# MCU.net
KiCad netlist of a schematic drawn in Altium Designer
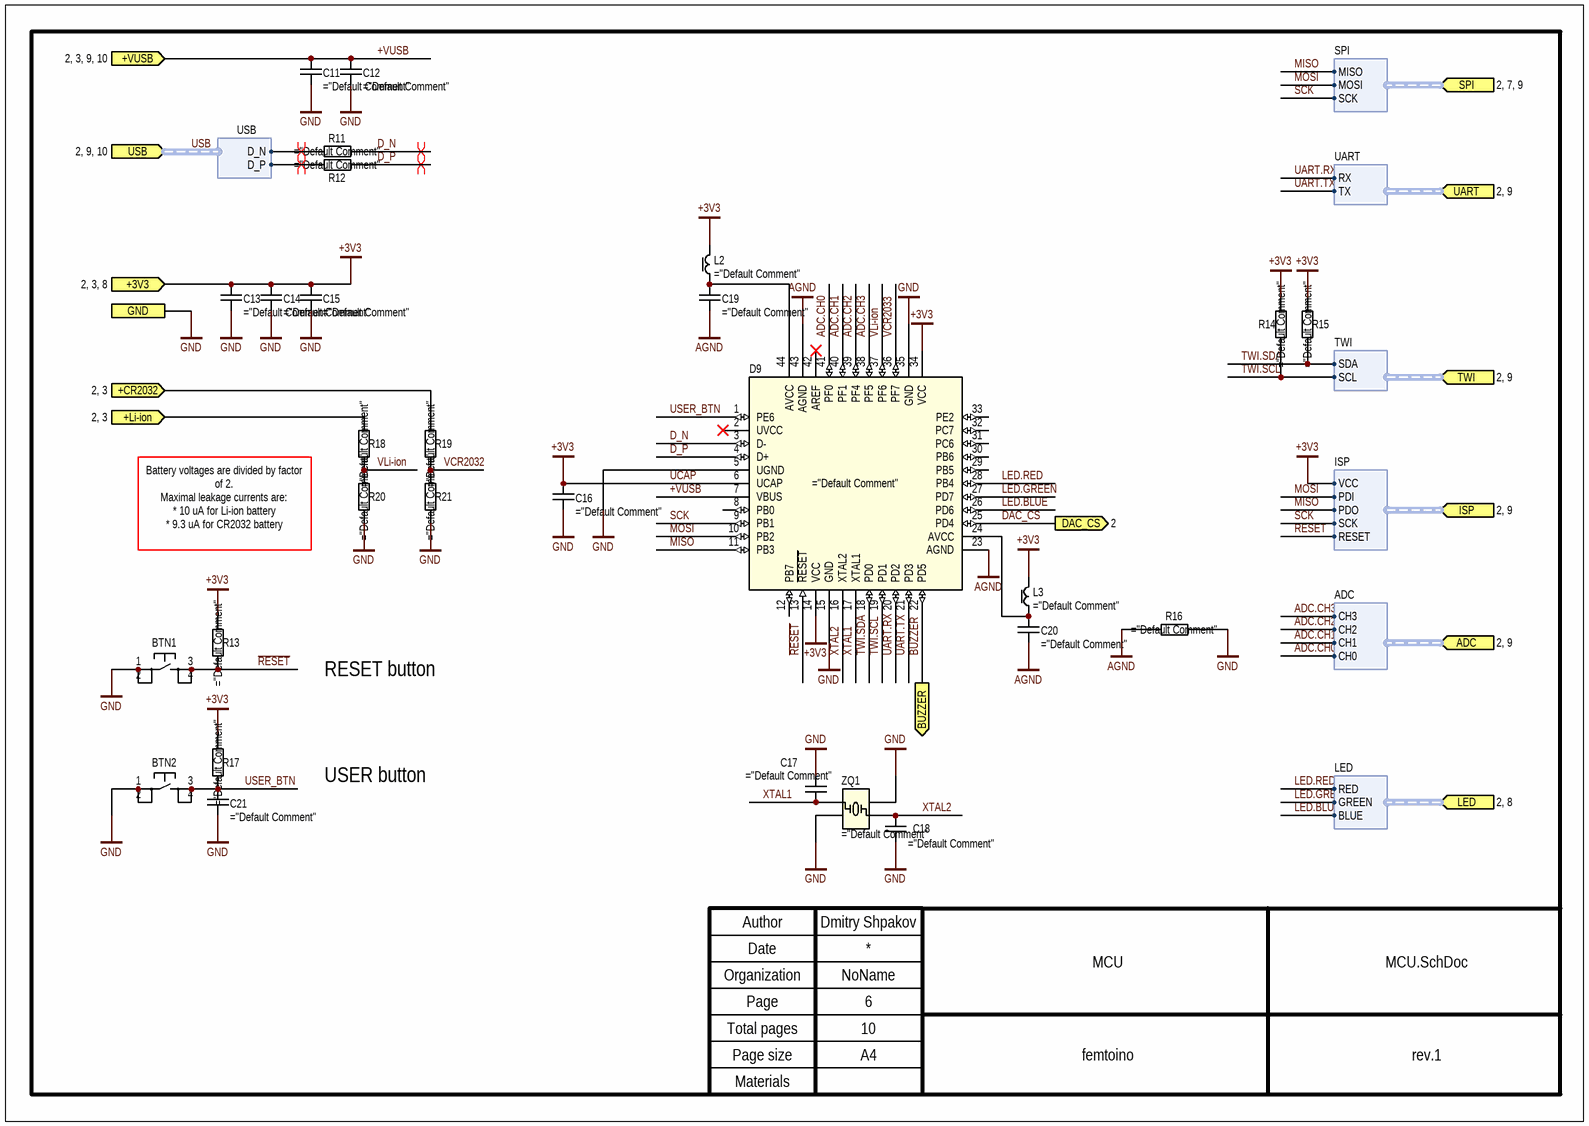
[diagram p0: MCU.SchDoc]

(export (version "E")
  (design (tool "Eeschema 10.0.6"))
  (components
    (comp (ref "BTN1")
      (value "~")
      (description "SWITCH TACTILE SPST-NO 0.05A 16V")
      (fields (field (name "TOLERANCE") "* %") (field (name "MANUFACTURER") "C&K"))
      (libsource (lib "femtoino") (part "PTS810 SJK 250 SMTR LFS"))
    )
    (comp (ref "BTN2")
      (value "~")
      (description "SWITCH TACTILE SPST-NO 0.05A 16V")
      (fields (field (name "TOLERANCE") "* %") (field (name "MANUFACTURER") "C&K"))
      (libsource (lib "femtoino") (part "PTS810 SJK 250 SMTR LFS"))
    )
    (comp (ref "C11")
      (value "~")
      (description "CAP CER 10UF 10V X5R 0805")
      (fields (field (name "TOLERANCE") "10 %") (field (name "MANUFACTURER") "YAGEO"))
      (libsource (lib "femtoino") (part "CC0805KPX5R6BB106"))
    )
    (comp (ref "C12")
      (value "~")
      (description "CAP CER 1UF 10V X5R 0805")
      (fields (field (name "TOLERANCE") "10 %") (field (name "MANUFACTURER") "YAGEO"))
      (libsource (lib "femtoino") (part "CC0805KKX5R6BB105"))
    )
    (comp (ref "C13")
      (value "~")
      (description "CAP CER 10UF 10V X5R 0805")
      (fields (field (name "TOLERANCE") "10 %") (field (name "MANUFACTURER") "YAGEO"))
      (libsource (lib "femtoino") (part "CC0805KPX5R6BB106"))
    )
    (comp (ref "C14")
      (value "~")
      (description "CAP CER 10UF 10V X5R 0805")
      (fields (field (name "TOLERANCE") "10 %") (field (name "MANUFACTURER") "YAGEO"))
      (libsource (lib "femtoino") (part "CC0805KPX5R6BB106"))
    )
    (comp (ref "C15")
      (value "~")
      (description "CAP CER 1UF 10V X5R 0805")
      (fields (field (name "TOLERANCE") "10 %") (field (name "MANUFACTURER") "YAGEO"))
      (libsource (lib "femtoino") (part "CC0805KKX5R6BB105"))
    )
    (comp (ref "C16")
      (value "~")
      (description "CAP CER 1UF 10V X5R 0805")
      (fields (field (name "TOLERANCE") "10 %") (field (name "MANUFACTURER") "YAGEO"))
      (libsource (lib "femtoino") (part "CC0805KKX5R6BB105"))
    )
    (comp (ref "C17")
      (value "~")
      (description "CAP CER 12PF 50V C0G/NPO 0603")
      (fields (field (name "TOLERANCE") "5 %") (field (name "MANUFACTURER") "YAGEO"))
      (libsource (lib "femtoino") (part "CC0603JRNPO9BN120"))
    )
    (comp (ref "C18")
      (value "~")
      (description "CAP CER 12PF 50V C0G/NPO 0603")
      (fields (field (name "TOLERANCE") "5 %") (field (name "MANUFACTURER") "YAGEO"))
      (libsource (lib "femtoino") (part "CC0603JRNPO9BN120"))
    )
    (comp (ref "C19")
      (value "~")
      (description "CAP CER 0.1UF 50V X7R 0805")
      (fields (field (name "TOLERANCE") "10 %") (field (name "MANUFACTURER") "YAGEO"))
      (libsource (lib "femtoino") (part "CC0805KRX7R9BB104"))
    )
    (comp (ref "C20")
      (value "~")
      (description "CAP CER 0.1UF 50V X7R 0805")
      (fields (field (name "TOLERANCE") "10 %") (field (name "MANUFACTURER") "YAGEO"))
      (libsource (lib "femtoino") (part "CC0805KRX7R9BB104"))
    )
    (comp (ref "C21")
      (value "~")
      (description "CAP CER 0.1UF 50V X7R 0805")
      (fields (field (name "TOLERANCE") "10 %") (field (name "MANUFACTURER") "YAGEO"))
      (libsource (lib "femtoino") (part "CC0805KRX7R9BB104"))
    )
    (comp (ref "D9")
      (value "~")
      (description "IC MCU 8BIT 32KB FLASH 44VQFN")
      (fields (field (name "TOLERANCE") "* %") (field (name "MANUFACTURER") "Microchip Technology"))
      (libsource (lib "femtoino") (part "ATMEGA32U4-MU"))
    )
    (comp (ref "L2")
      (value "~")
      (description "FIXED IND 10UH 850MA 300MOHM SMD")
      (fields (field (name "TOLERANCE") "* %") (field (name "MANUFACTURER") "Würth Elektronik"))
      (libsource (lib "femtoino") (part "74479887310A"))
    )
    (comp (ref "L3")
      (value "~")
      (description "FIXED IND 10UH 850MA 300MOHM SMD")
      (fields (field (name "TOLERANCE") "* %") (field (name "MANUFACTURER") "Würth Elektronik"))
      (libsource (lib "femtoino") (part "74479887310A"))
    )
    (comp (ref "R11")
      (value "~")
      (description "RES 22 OHM 1% 1/10W 0603")
      (fields (field (name "TOLERANCE") "1 %") (field (name "MANUFACTURER") "YAGEO"))
      (libsource (lib "femtoino") (part "RC0603FR-0722RL"))
    )
    (comp (ref "R12")
      (value "~")
      (description "RES 22 OHM 1% 1/10W 0603")
      (fields (field (name "TOLERANCE") "1 %") (field (name "MANUFACTURER") "YAGEO"))
      (libsource (lib "femtoino") (part "RC0603FR-0722RL"))
    )
    (comp (ref "R13")
      (value "~")
      (description "RES 62K OHM 1% 1/10W 0603")
      (fields (field (name "TOLERANCE") "1 %") (field (name "MANUFACTURER") "YAGEO"))
      (libsource (lib "femtoino") (part "RC0603FR-0762KL"))
    )
    (comp (ref "R14")
      (value "~")
      (description "RES 5.1K OHM 1% 1/10W 0603")
      (fields (field (name "TOLERANCE") "1 %") (field (name "MANUFACTURER") "YAGEO"))
      (libsource (lib "femtoino") (part "RC0603FR-075K1L"))
    )
    (comp (ref "R15")
      (value "~")
      (description "RES 5.1K OHM 1% 1/10W 0603")
      (fields (field (name "TOLERANCE") "1 %") (field (name "MANUFACTURER") "YAGEO"))
      (libsource (lib "femtoino") (part "RC0603FR-075K1L"))
    )
    (comp (ref "R16")
      (value "~")
      (description "RES 0 OHM JUMPER 1/10W 0603")
      (fields (field (name "TOLERANCE") "* %") (field (name "MANUFACTURER") "YAGEO"))
      (libsource (lib "femtoino") (part "RC0603JR-070RL"))
    )
    (comp (ref "R17")
      (value "~")
      (description "RES 62K OHM 1% 1/10W 0603")
      (fields (field (name "TOLERANCE") "1 %") (field (name "MANUFACTURER") "YAGEO"))
      (libsource (lib "femtoino") (part "RC0603FR-0762KL"))
    )
    (comp (ref "R18")
      (value "~")
      (description "RES 200K OHM 1% 1/10W 0603")
      (fields (field (name "TOLERANCE") "1 %") (field (name "MANUFACTURER") "YAGEO"))
      (libsource (lib "femtoino") (part "RC0603FR-07200KL"))
    )
    (comp (ref "R19")
      (value "~")
      (description "RES 200K OHM 1% 1/10W 0603")
      (fields (field (name "TOLERANCE") "1 %") (field (name "MANUFACTURER") "YAGEO"))
      (libsource (lib "femtoino") (part "RC0603FR-07200KL"))
    )
    (comp (ref "R20")
      (value "~")
      (description "RES 200K OHM 1% 1/10W 0603")
      (fields (field (name "TOLERANCE") "1 %") (field (name "MANUFACTURER") "YAGEO"))
      (libsource (lib "femtoino") (part "RC0603FR-07200KL"))
    )
    (comp (ref "R21")
      (value "~")
      (description "RES 200K OHM 1% 1/10W 0603")
      (fields (field (name "TOLERANCE") "1 %") (field (name "MANUFACTURER") "YAGEO"))
      (libsource (lib "femtoino") (part "RC0603FR-07200KL"))
    )
    (comp (ref "ZQ1")
      (value "~")
      (description "CRYSTAL 8.0000MHZ 12PF SMD")
      (fields (field (name "TOLERANCE") "20 ppm") (field (name "MANUFACTURER") "ECS Inc."))
      (libsource (lib "femtoino") (part "ECS-80-12-33-JGN-TR"))
    )
  )
  (nets
    (net (code "8") (name "+3V3") (class "Default")
      (node (ref "C13") (pin "2") (pinfunction "2_2") (pintype "passive"))
      (node (ref "C14") (pin "2") (pinfunction "2_2") (pintype "passive"))
      (node (ref "C15") (pin "2") (pinfunction "2_2") (pintype "passive"))
      (node (ref "C16") (pin "2") (pinfunction "2_2") (pintype "passive"))
      (node (ref "D9") (pin "14") (pinfunction "VCC_14") (pintype "passive"))
      (node (ref "D9") (pin "34") (pinfunction "VCC_34") (pintype "passive"))
      (node (ref "D9") (pin "6") (pinfunction "UCAP_6") (pintype "passive"))
      (node (ref "L2") (pin "2") (pinfunction "2_2") (pintype "passive"))
      (node (ref "L3") (pin "2") (pinfunction "2_2") (pintype "passive"))
      (node (ref "R13") (pin "2") (pinfunction "2_2") (pintype "passive"))
      (node (ref "R14") (pin "2") (pinfunction "2_2") (pintype "passive"))
      (node (ref "R15") (pin "2") (pinfunction "2_2") (pintype "passive"))
      (node (ref "R17") (pin "2") (pinfunction "2_2") (pintype "passive"))
    )
    (net (code "9") (name "/+CR2032") (class "Default")
      (node (ref "R19") (pin "2") (pinfunction "2_2") (pintype "passive"))
    )
    (net (code "10") (name "/+Li-ion") (class "Default")
      (node (ref "R18") (pin "2") (pinfunction "2_2") (pintype "passive"))
    )
    (net (code "11") (name "/+VUSB") (class "Default")
      (node (ref "C11") (pin "2") (pinfunction "2_2") (pintype "passive"))
      (node (ref "C12") (pin "2") (pinfunction "2_2") (pintype "passive"))
      (node (ref "D9") (pin "7") (pinfunction "VBUS_7") (pintype "passive"))
    )
    (net (code "12") (name "/ADC.CH0") (class "Default")
      (node (ref "D9") (pin "41") (pinfunction "PF0_41") (pintype "bidirectional"))
    )
    (net (code "13") (name "/ADC.CH1") (class "Default")
      (node (ref "D9") (pin "40") (pinfunction "PF1_40") (pintype "bidirectional"))
    )
    (net (code "14") (name "/ADC.CH2") (class "Default")
      (node (ref "D9") (pin "39") (pinfunction "PF4_39") (pintype "bidirectional"))
    )
    (net (code "15") (name "/ADC.CH3") (class "Default")
      (node (ref "D9") (pin "38") (pinfunction "PF5_38") (pintype "bidirectional"))
    )
    (net (code "16") (name "/BUZZER") (class "Default")
      (node (ref "D9") (pin "22") (pinfunction "PD5_22") (pintype "bidirectional"))
    )
    (net (code "17") (name "/DAC_CS") (class "Default")
      (node (ref "D9") (pin "25") (pinfunction "PD4_25") (pintype "bidirectional"))
    )
    (net (code "18") (name "/D_N") (class "Default")
      (node (ref "D9") (pin "3") (pinfunction "D-_3") (pintype "bidirectional"))
      (node (ref "R11") (pin "2") (pinfunction "2_2") (pintype "passive"))
    )
    (net (code "19") (name "/D_P") (class "Default")
      (node (ref "D9") (pin "4") (pinfunction "D+_4") (pintype "bidirectional"))
      (node (ref "R12") (pin "2") (pinfunction "2_2") (pintype "passive"))
    )
    (net (code "20") (name "/LED.BLUE") (class "Default")
      (node (ref "D9") (pin "26") (pinfunction "PD6_26") (pintype "bidirectional"))
    )
    (net (code "21") (name "/LED.GREEN") (class "Default")
      (node (ref "D9") (pin "27") (pinfunction "PD7_27") (pintype "bidirectional"))
    )
    (net (code "22") (name "/LED.RED") (class "Default")
      (node (ref "D9") (pin "28") (pinfunction "PB4_28") (pintype "bidirectional"))
    )
    (net (code "23") (name "/MISO") (class "Default")
      (node (ref "D9") (pin "11") (pinfunction "PB3_11") (pintype "bidirectional"))
    )
    (net (code "24") (name "/MOSI") (class "Default")
      (node (ref "D9") (pin "10") (pinfunction "PB2_10") (pintype "bidirectional"))
    )
    (net (code "25") (name "/SCK") (class "Default")
      (node (ref "D9") (pin "9") (pinfunction "PB1_9") (pintype "bidirectional"))
    )
    (net (code "26") (name "/TWI.SCL") (class "Default")
      (node (ref "D9") (pin "19") (pinfunction "PD1_19") (pintype "bidirectional"))
      (node (ref "R14") (pin "1") (pinfunction "1_1") (pintype "passive"))
    )
    (net (code "27") (name "/TWI.SDA") (class "Default")
      (node (ref "D9") (pin "18") (pinfunction "PD0_18") (pintype "bidirectional"))
      (node (ref "R15") (pin "1") (pinfunction "1_1") (pintype "passive"))
    )
    (net (code "28") (name "/UART.RX") (class "Default")
      (node (ref "D9") (pin "20") (pinfunction "PD2_20") (pintype "bidirectional"))
    )
    (net (code "29") (name "/UART.TX") (class "Default")
      (node (ref "D9") (pin "21") (pinfunction "PD3_21") (pintype "bidirectional"))
    )
    (net (code "31") (name "/USER_BTN") (class "Default")
      (node (ref "BTN2") (pin "3") (pinfunction "3_3") (pintype "passive"))
      (node (ref "BTN2") (pin "4") (pinfunction "4_4") (pintype "passive"))
      (node (ref "C21") (pin "2") (pinfunction "2_2") (pintype "passive"))
      (node (ref "D9") (pin "1") (pinfunction "PE6_1") (pintype "bidirectional"))
      (node (ref "R17") (pin "1") (pinfunction "1_1") (pintype "passive"))
    )
    (net (code "32") (name "/VCR2032") (class "Default")
      (node (ref "R19") (pin "1") (pinfunction "1_1") (pintype "passive"))
      (node (ref "R21") (pin "2") (pinfunction "2_2") (pintype "passive"))
    )
    (net (code "33") (name "/VCR2033") (class "Default")
      (node (ref "D9") (pin "36") (pinfunction "PF7_36") (pintype "bidirectional"))
    )
    (net (code "34") (name "/VLi-ion") (class "Default")
      (node (ref "D9") (pin "37") (pinfunction "PF6_37") (pintype "bidirectional"))
      (node (ref "R18") (pin "1") (pinfunction "1_1") (pintype "passive"))
      (node (ref "R20") (pin "2") (pinfunction "2_2") (pintype "passive"))
    )
    (net (code "35") (name "/XTAL1") (class "Default")
      (node (ref "C17") (pin "2") (pinfunction "2_2") (pintype "passive"))
      (node (ref "D9") (pin "17") (pinfunction "XTAL1_17") (pintype "passive"))
      (node (ref "ZQ1") (pin "1") (pinfunction "1_1") (pintype "passive"))
    )
    (net (code "36") (name "/XTAL2") (class "Default")
      (node (ref "C18") (pin "2") (pinfunction "2_2") (pintype "passive"))
      (node (ref "D9") (pin "16") (pinfunction "XTAL2_16") (pintype "passive"))
      (node (ref "ZQ1") (pin "3") (pinfunction "3_3") (pintype "passive"))
    )
    (net (code "43") (name "/~{RESET}") (class "Default")
      (node (ref "BTN1") (pin "3") (pinfunction "3_3") (pintype "passive"))
      (node (ref "BTN1") (pin "4") (pinfunction "4_4") (pintype "passive"))
      (node (ref "D9") (pin "13") (pinfunction "~{RESET}_13") (pintype "input"))
      (node (ref "R13") (pin "1") (pinfunction "1_1") (pintype "passive"))
    )
    (net (code "44") (name "AGND") (class "Default")
      (node (ref "C19") (pin "1") (pinfunction "1_1") (pintype "passive"))
      (node (ref "C20") (pin "1") (pinfunction "1_1") (pintype "passive"))
      (node (ref "D9") (pin "23") (pinfunction "AGND_23") (pintype "passive"))
      (node (ref "D9") (pin "43") (pinfunction "AGND_43") (pintype "passive"))
      (node (ref "R16") (pin "1") (pinfunction "1_1") (pintype "passive"))
    )
    (net (code "45") (name "GND") (class "Default")
      (node (ref "BTN1") (pin "1") (pinfunction "1_1") (pintype "passive"))
      (node (ref "BTN1") (pin "2") (pinfunction "2_2") (pintype "passive"))
      (node (ref "BTN2") (pin "1") (pinfunction "1_1") (pintype "passive"))
      (node (ref "BTN2") (pin "2") (pinfunction "2_2") (pintype "passive"))
      (node (ref "C11") (pin "1") (pinfunction "1_1") (pintype "passive"))
      (node (ref "C12") (pin "1") (pinfunction "1_1") (pintype "passive"))
      (node (ref "C13") (pin "1") (pinfunction "1_1") (pintype "passive"))
      (node (ref "C14") (pin "1") (pinfunction "1_1") (pintype "passive"))
      (node (ref "C15") (pin "1") (pinfunction "1_1") (pintype "passive"))
      (node (ref "C16") (pin "1") (pinfunction "1_1") (pintype "passive"))
      (node (ref "C17") (pin "1") (pinfunction "1_1") (pintype "passive"))
      (node (ref "C18") (pin "1") (pinfunction "1_1") (pintype "passive"))
      (node (ref "C21") (pin "1") (pinfunction "1_1") (pintype "passive"))
      (node (ref "D9") (pin "15") (pinfunction "GND_15") (pintype "passive"))
      (node (ref "D9") (pin "35") (pinfunction "GND_35") (pintype "passive"))
      (node (ref "D9") (pin "5") (pinfunction "UGND_5") (pintype "passive"))
      (node (ref "R16") (pin "2") (pinfunction "2_2") (pintype "passive"))
      (node (ref "R20") (pin "1") (pinfunction "1_1") (pintype "passive"))
      (node (ref "R21") (pin "1") (pinfunction "1_1") (pintype "passive"))
      (node (ref "ZQ1") (pin "2") (pinfunction "2_2") (pintype "passive"))
      (node (ref "ZQ1") (pin "4") (pinfunction "4_4") (pintype "passive"))
    )
    (net (code "46") (name "Net-(C19-Pad2)") (class "Default")
      (node (ref "C19") (pin "2") (pinfunction "2_2") (pintype "passive"))
      (node (ref "D9") (pin "44") (pinfunction "AVCC_44") (pintype "passive"))
      (node (ref "L2") (pin "1") (pinfunction "1_1") (pintype "passive"))
    )
    (net (code "47") (name "Net-(C20-Pad2)") (class "Default")
      (node (ref "C20") (pin "2") (pinfunction "2_2") (pintype "passive"))
      (node (ref "D9") (pin "24") (pinfunction "AVCC_24") (pintype "passive"))
      (node (ref "L3") (pin "1") (pinfunction "1_1") (pintype "passive"))
    )
    (net (code "48") (name "unconnected-(D9-AREF-Pad42)") (class "Default")
      (node (ref "D9") (pin "42") (pinfunction "AREF_42") (pintype "passive+no_connect"))
    )
    (net (code "49") (name "unconnected-(D9-PB0-Pad8)") (class "Default")
      (node (ref "D9") (pin "8") (pinfunction "PB0_8") (pintype "bidirectional"))
    )
    (net (code "50") (name "unconnected-(D9-PB5-Pad29)") (class "Default")
      (node (ref "D9") (pin "29") (pinfunction "PB5_29") (pintype "bidirectional"))
    )
    (net (code "51") (name "unconnected-(D9-PB6-Pad30)") (class "Default")
      (node (ref "D9") (pin "30") (pinfunction "PB6_30") (pintype "bidirectional"))
    )
    (net (code "52") (name "unconnected-(D9-PB7-Pad12)") (class "Default")
      (node (ref "D9") (pin "12") (pinfunction "PB7_12") (pintype "bidirectional"))
    )
    (net (code "53") (name "unconnected-(D9-PC6-Pad31)") (class "Default")
      (node (ref "D9") (pin "31") (pinfunction "PC6_31") (pintype "bidirectional"))
    )
    (net (code "54") (name "unconnected-(D9-PC7-Pad32)") (class "Default")
      (node (ref "D9") (pin "32") (pinfunction "PC7_32") (pintype "bidirectional"))
    )
    (net (code "55") (name "unconnected-(D9-PE2-Pad33)") (class "Default")
      (node (ref "D9") (pin "33") (pinfunction "PE2_33") (pintype "bidirectional"))
    )
    (net (code "56") (name "unconnected-(D9-UVCC-Pad2)") (class "Default")
      (node (ref "D9") (pin "2") (pinfunction "UVCC_2") (pintype "passive+no_connect"))
    )
    (net (code "57") (name "unconnected-(R11-Pad1)") (class "Default")
      (node (ref "R11") (pin "1") (pinfunction "1_1") (pintype "passive"))
    )
    (net (code "58") (name "unconnected-(R12-Pad1)") (class "Default")
      (node (ref "R12") (pin "1") (pinfunction "1_1") (pintype "passive"))
    )
  )
)
